# ORD_PT2399.net
KiCad netlist of a schematic drawn in Altium Designer
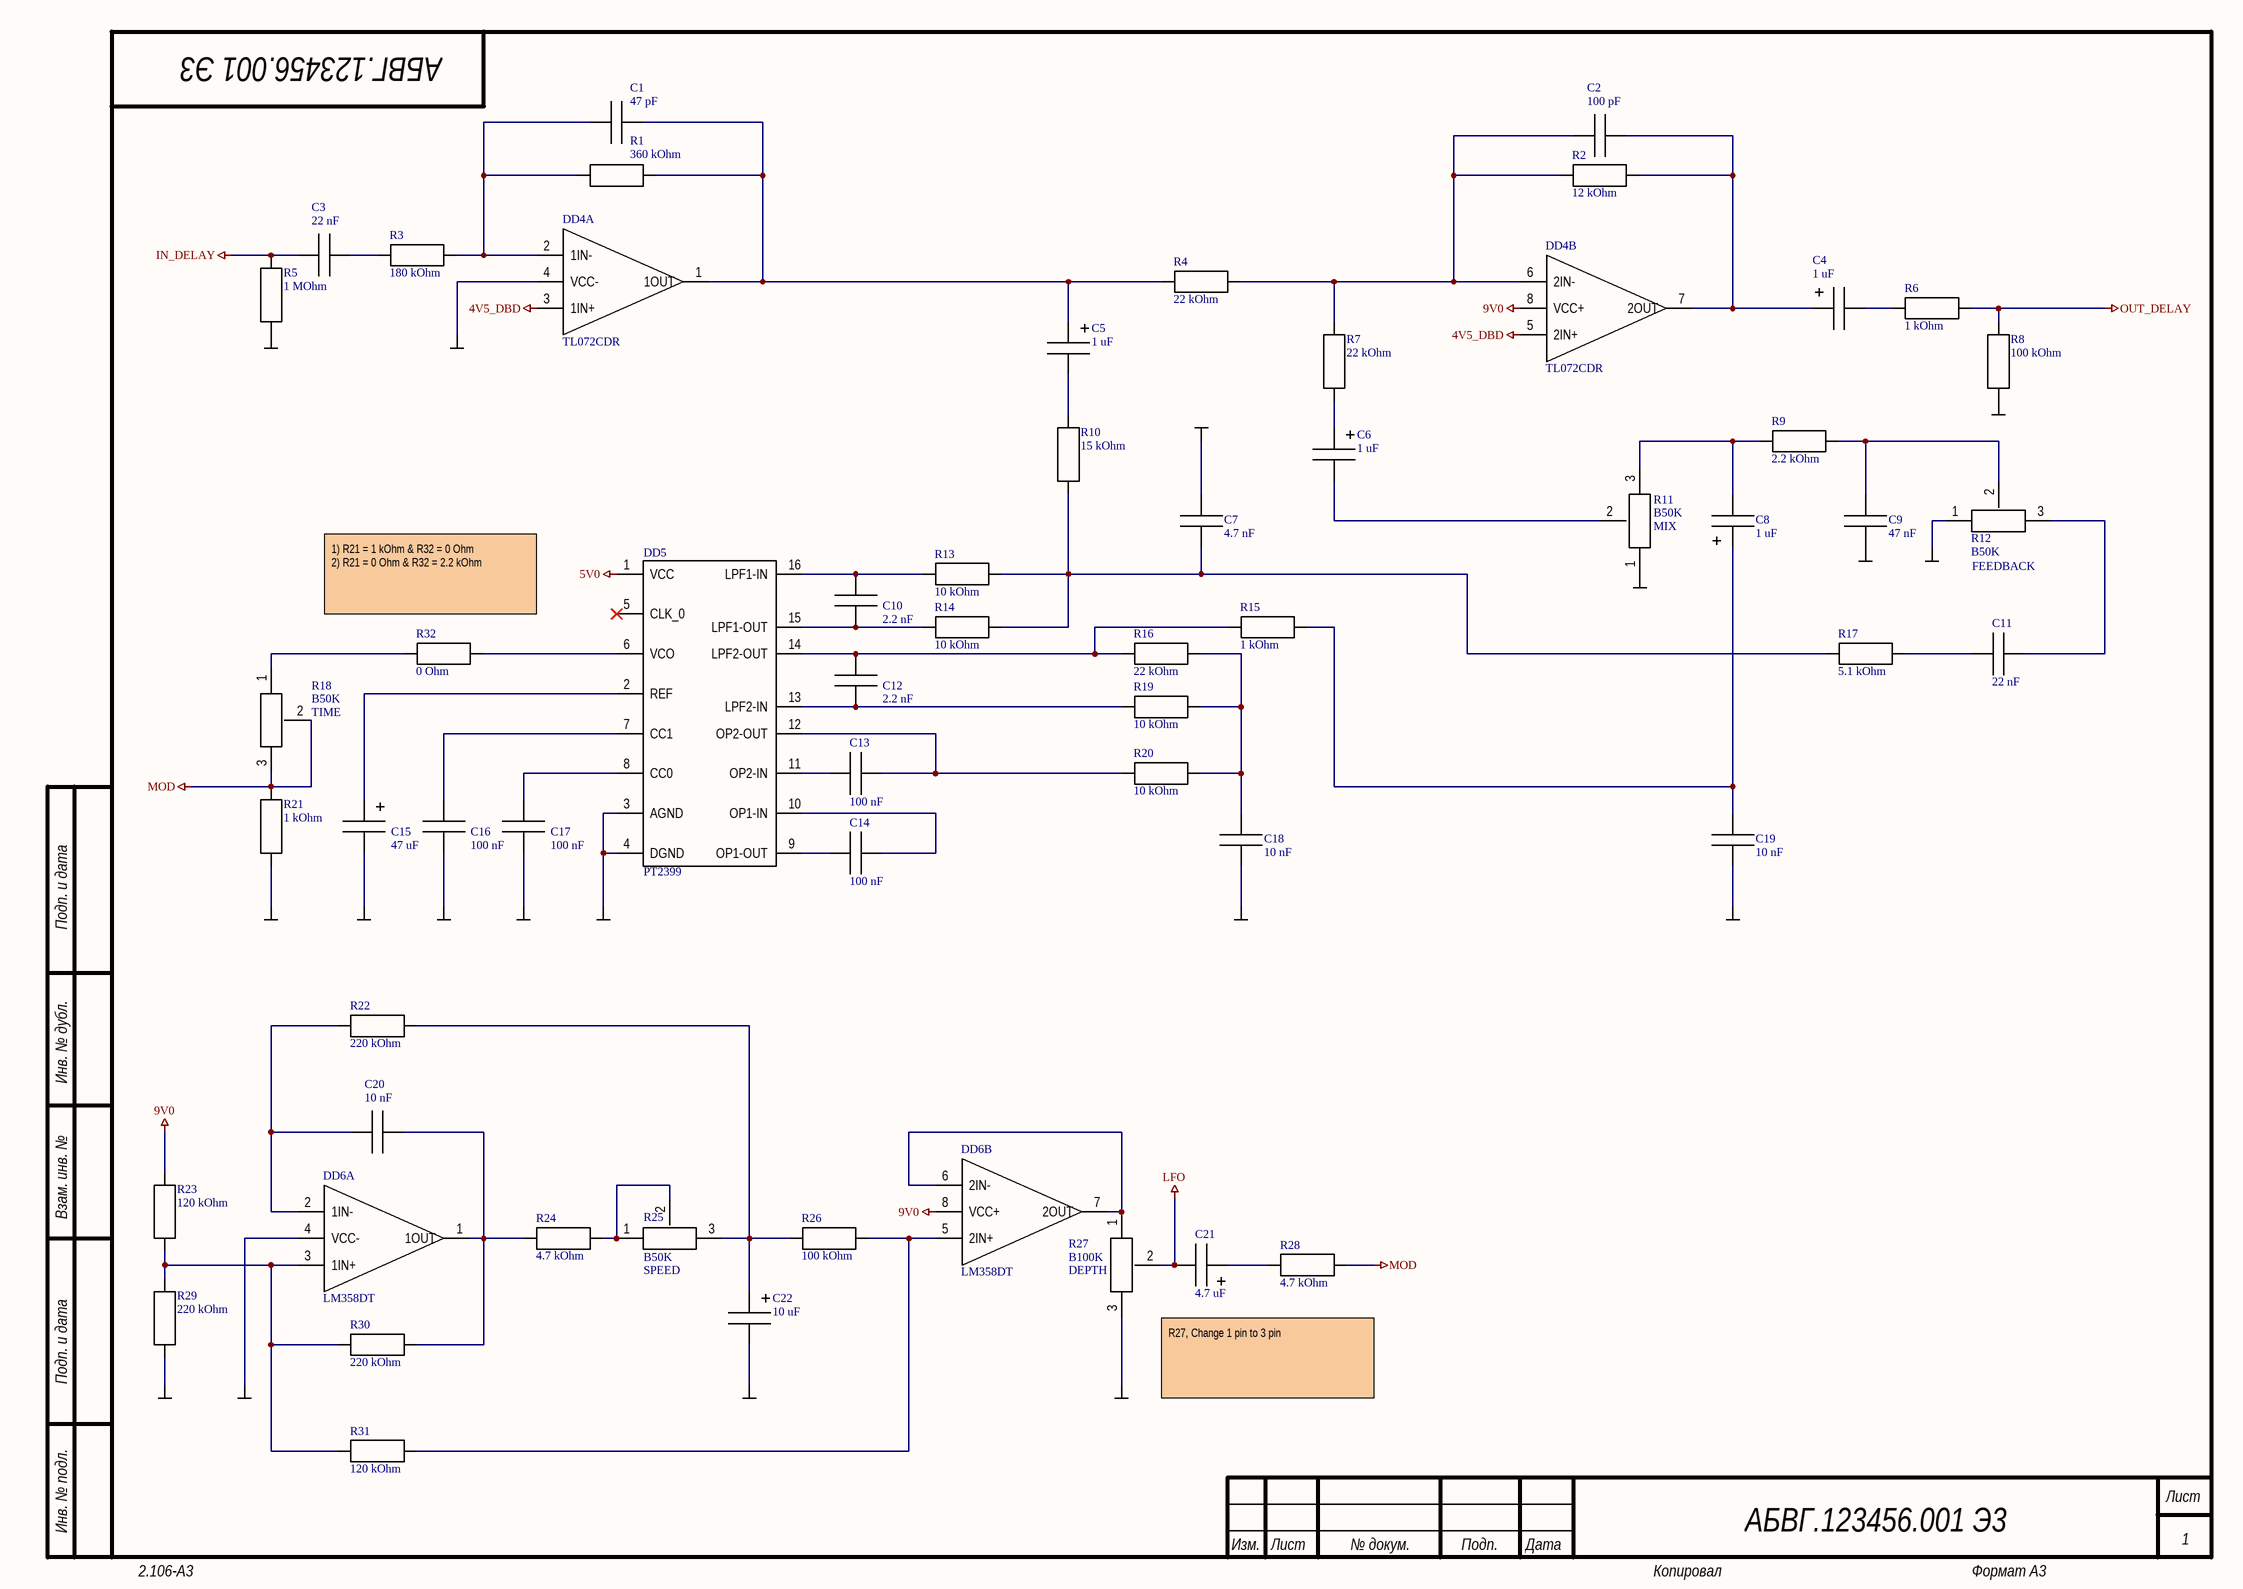
[diagram p0: ORD_PT2399.SchDoc]

(export (version "E")
  (design (tool "Eeschema 10.0.6"))
  (components
    (comp (ref "C1")
      (value "47 pF")
      (footprint "C0805[2012]")
      (libsource (lib "Gost_passive_lib") (part "Capacitor"))
    )
    (comp (ref "C2")
      (value "100 pF")
      (footprint "C0805[2012]")
      (libsource (lib "Gost_passive_lib") (part "Capacitor"))
    )
    (comp (ref "C3")
      (value "22 nF")
      (footprint "C0805[2012]")
      (libsource (lib "Gost_passive_lib") (part "Capacitor"))
    )
    (comp (ref "C4")
      (value "1 uF")
      (footprint "C3216_CASE-A")
      (libsource (lib "Gost_passive_lib") (part "Capacitor_Pol"))
    )
    (comp (ref "C5")
      (value "1 uF")
      (footprint "C3216_CASE-A")
      (libsource (lib "Gost_passive_lib") (part "Capacitor_Pol"))
    )
    (comp (ref "C6")
      (value "1 uF")
      (footprint "C3216_CASE-A")
      (libsource (lib "Gost_passive_lib") (part "Capacitor_Pol"))
    )
    (comp (ref "C7")
      (value "4.7 nF")
      (footprint "C0805[2012]")
      (libsource (lib "Gost_passive_lib") (part "Capacitor"))
    )
    (comp (ref "C8")
      (value "1 uF")
      (footprint "C3216_CASE-A")
      (libsource (lib "Gost_passive_lib") (part "Capacitor_Pol"))
    )
    (comp (ref "C9")
      (value "47 nF")
      (footprint "C0805[2012]")
      (libsource (lib "Gost_passive_lib") (part "Capacitor"))
    )
    (comp (ref "C10")
      (value "2.2 nF")
      (footprint "C0805[2012]")
      (libsource (lib "Gost_passive_lib") (part "Capacitor"))
    )
    (comp (ref "C11")
      (value "22 nF")
      (footprint "C0805[2012]")
      (libsource (lib "Gost_passive_lib") (part "Capacitor"))
    )
    (comp (ref "C12")
      (value "2.2 nF")
      (footprint "C0805[2012]")
      (libsource (lib "Gost_passive_lib") (part "Capacitor"))
    )
    (comp (ref "C13")
      (value "100 nF")
      (footprint "C0805[2012]")
      (libsource (lib "Gost_passive_lib") (part "Capacitor"))
    )
    (comp (ref "C14")
      (value "100 nF")
      (footprint "C0805[2012]")
      (libsource (lib "Gost_passive_lib") (part "Capacitor"))
    )
    (comp (ref "C15")
      (value "47 uF")
      (footprint "C3216_CASE-A")
      (libsource (lib "Gost_passive_lib") (part "Capacitor_Pol"))
    )
    (comp (ref "C16")
      (value "100 nF")
      (footprint "C0805[2012]")
      (libsource (lib "Gost_passive_lib") (part "Capacitor"))
    )
    (comp (ref "C17")
      (value "100 nF")
      (footprint "C0805[2012]")
      (libsource (lib "Gost_passive_lib") (part "Capacitor"))
    )
    (comp (ref "C18")
      (value "10 nF")
      (footprint "C0805[2012]")
      (libsource (lib "Gost_passive_lib") (part "Capacitor"))
    )
    (comp (ref "C19")
      (value "10 nF")
      (footprint "C0805[2012]")
      (libsource (lib "Gost_passive_lib") (part "Capacitor"))
    )
    (comp (ref "C20")
      (value "10 nF")
      (footprint "C0805[2012]")
      (libsource (lib "Gost_passive_lib") (part "Capacitor"))
    )
    (comp (ref "C21")
      (value "4.7 uF")
      (footprint "C3216_CASE-A")
      (libsource (lib "Gost_passive_lib") (part "Capacitor_Pol"))
    )
    (comp (ref "C22")
      (value "10 uF")
      (footprint "C3216_CASE-A")
      (libsource (lib "Gost_passive_lib") (part "Capacitor_Pol"))
    )
    (comp (ref "DD4")
      (value "TL072CDR")
      (footprint "SO8")
      (description "TL072CDR, Dual Operational Amplifier 4 MHz -18 to 18V, 8-Pin SO")
      (fields
        (field (name "MANUFACTURER_PART_NUMBER") "LM358DT")
        (field (name "MOUSER PART NUMBER") "511-LM358DT")
      )
      (libsource (lib "Gost_active_libs") (part "TL072CDR"))
    )
    (comp (ref "DD5")
      (value "PT2399")
      (footprint "DIP16_with_Socket")
      (description "Echo Processor IC")
      (libsource (lib "Gost_active_libs") (part "PT2399"))
    )
    (comp (ref "DD6")
      (value "LM358DT")
      (footprint "SO8")
      (description "LM358DT, Dual Operational Amplifier 1.1MHz 5 to 28V, 8-Pin SO")
      (fields (field (name "MOUSER PART NUMBER") "511-LM358DT") (field (name "RS PART NUMBER") "7140827P"))
      (libsource (lib "Gost_active_libs") (part "LM358DT"))
    )
    (comp (ref "R1")
      (value "360 kOhm")
      (footprint "R0805[2012]")
      (libsource (lib "Gost_passive_lib") (part "Resistor"))
    )
    (comp (ref "R2")
      (value "12 kOhm")
      (footprint "R0805[2012]")
      (libsource (lib "Gost_passive_lib") (part "Resistor"))
    )
    (comp (ref "R3")
      (value "180 kOhm")
      (footprint "R0805[2012]")
      (libsource (lib "Gost_passive_lib") (part "Resistor"))
    )
    (comp (ref "R4")
      (value "22 kOhm")
      (footprint "R0805[2012]")
      (libsource (lib "Gost_passive_lib") (part "Resistor"))
    )
    (comp (ref "R5")
      (value "1 MOhm")
      (footprint "R0805[2012]")
      (libsource (lib "Gost_passive_lib") (part "Resistor"))
    )
    (comp (ref "R6")
      (value "1 kOhm")
      (footprint "R0805[2012]")
      (libsource (lib "Gost_passive_lib") (part "Resistor"))
    )
    (comp (ref "R7")
      (value "22 kOhm")
      (footprint "R0805[2012]")
      (libsource (lib "Gost_passive_lib") (part "Resistor"))
    )
    (comp (ref "R8")
      (value "100 kOhm")
      (footprint "R0805[2012]")
      (libsource (lib "Gost_passive_lib") (part "Resistor"))
    )
    (comp (ref "R9")
      (value "2.2 kOhm")
      (footprint "R0805[2012]")
      (libsource (lib "Gost_passive_lib") (part "Resistor"))
    )
    (comp (ref "R10")
      (value "15 kOhm")
      (footprint "R0805[2012]")
      (libsource (lib "Gost_passive_lib") (part "Resistor"))
    )
    (comp (ref "R11")
      (value "B50K")
      (footprint "16K1")
      (libsource (lib "Gost_passive_lib") (part "16K1-B (Pot)"))
    )
    (comp (ref "R12")
      (value "B50K")
      (footprint "16K1")
      (libsource (lib "Gost_passive_lib") (part "16K1-B (Pot)"))
    )
    (comp (ref "R13")
      (value "10 kOhm")
      (footprint "R0805[2012]")
      (libsource (lib "Gost_passive_lib") (part "Resistor"))
    )
    (comp (ref "R14")
      (value "10 kOhm")
      (footprint "R0805[2012]")
      (libsource (lib "Gost_passive_lib") (part "Resistor"))
    )
    (comp (ref "R15")
      (value "1 kOhm")
      (footprint "R0805[2012]")
      (libsource (lib "Gost_passive_lib") (part "Resistor"))
    )
    (comp (ref "R16")
      (value "22 kOhm")
      (footprint "R0805[2012]")
      (libsource (lib "Gost_passive_lib") (part "Resistor"))
    )
    (comp (ref "R17")
      (value "5.1 kOhm")
      (footprint "R0805[2012]")
      (libsource (lib "Gost_passive_lib") (part "Resistor"))
    )
    (comp (ref "R18")
      (value "B50K")
      (footprint "16K1")
      (libsource (lib "Gost_passive_lib") (part "16K1-B (Pot)"))
    )
    (comp (ref "R19")
      (value "10 kOhm")
      (footprint "R0805[2012]")
      (libsource (lib "Gost_passive_lib") (part "Resistor"))
    )
    (comp (ref "R20")
      (value "10 kOhm")
      (footprint "R0805[2012]")
      (libsource (lib "Gost_passive_lib") (part "Resistor"))
    )
    (comp (ref "R21")
      (value "1 kOhm")
      (footprint "R0805[2012]")
      (libsource (lib "Gost_passive_lib") (part "Resistor"))
    )
    (comp (ref "R22")
      (value "220 kOhm")
      (footprint "R0805[2012]")
      (libsource (lib "Gost_passive_lib") (part "Resistor"))
    )
    (comp (ref "R23")
      (value "120 kOhm")
      (footprint "R0805[2012]")
      (libsource (lib "Gost_passive_lib") (part "Resistor"))
    )
    (comp (ref "R24")
      (value "4.7 kOhm")
      (footprint "R0805[2012]")
      (libsource (lib "Gost_passive_lib") (part "Resistor"))
    )
    (comp (ref "R25")
      (value "B50K")
      (footprint "16K1")
      (libsource (lib "Gost_passive_lib") (part "16K1-B (Pot)"))
    )
    (comp (ref "R26")
      (value "100 kOhm")
      (footprint "R0805[2012]")
      (libsource (lib "Gost_passive_lib") (part "Resistor"))
    )
    (comp (ref "R27")
      (value "B100K")
      (footprint "16K1")
      (libsource (lib "Gost_passive_lib") (part "16K1-B (Pot)"))
    )
    (comp (ref "R28")
      (value "4.7 kOhm")
      (footprint "R0805[2012]")
      (libsource (lib "Gost_passive_lib") (part "Resistor"))
    )
    (comp (ref "R29")
      (value "220 kOhm")
      (footprint "R0805[2012]")
      (libsource (lib "Gost_passive_lib") (part "Resistor"))
    )
    (comp (ref "R30")
      (value "220 kOhm")
      (footprint "R0805[2012]")
      (libsource (lib "Gost_passive_lib") (part "Resistor"))
    )
    (comp (ref "R31")
      (value "120 kOhm")
      (footprint "R0805[2012]")
      (libsource (lib "Gost_passive_lib") (part "Resistor"))
    )
    (comp (ref "R32")
      (value "0 Ohm")
      (footprint "R0805[2012]")
      (libsource (lib "Gost_passive_lib") (part "Resistor"))
    )
  )
  (nets
    (net (code "1") (name "4V5_DBD") (class "Default")
      (node (ref "DD4") (pin "3") (pinfunction "1IN+_3") (pintype "passive"))
      (node (ref "DD4") (pin "5") (pinfunction "2IN+_5") (pintype "passive"))
    )
    (net (code "2") (name "5V0") (class "Default")
      (node (ref "DD5") (pin "1") (pinfunction "VCC_1") (pintype "power_in"))
    )
    (net (code "3") (name "9V0") (class "Default")
      (node (ref "DD4") (pin "8") (pinfunction "VCC+_8") (pintype "power_in"))
      (node (ref "DD6") (pin "8") (pinfunction "VCC+_8") (pintype "power_in"))
      (node (ref "R23") (pin "1") (pinfunction "1_1") (pintype "passive"))
    )
    (net (code "4") (name "GND") (class "Default")
      (node (ref "C15") (pin "2") (pinfunction "2_2") (pintype "passive"))
      (node (ref "C16") (pin "1") (pinfunction "1_1") (pintype "passive"))
      (node (ref "C17") (pin "1") (pinfunction "1_1") (pintype "passive"))
      (node (ref "C18") (pin "2") (pinfunction "2_2") (pintype "passive"))
      (node (ref "C19") (pin "2") (pinfunction "2_2") (pintype "passive"))
      (node (ref "C22") (pin "2") (pinfunction "2_2") (pintype "passive"))
      (node (ref "C7") (pin "1") (pinfunction "1_1") (pintype "passive"))
      (node (ref "C9") (pin "2") (pinfunction "2_2") (pintype "passive"))
      (node (ref "DD4") (pin "4") (pinfunction "VCC-_4") (pintype "power_in"))
      (node (ref "DD5") (pin "3") (pinfunction "AGND_3") (pintype "passive"))
      (node (ref "DD5") (pin "4") (pinfunction "DGND_4") (pintype "passive"))
      (node (ref "DD6") (pin "4") (pinfunction "VCC-_4") (pintype "power_in"))
      (node (ref "R11") (pin "1") (pinfunction "1_1") (pintype "passive"))
      (node (ref "R12") (pin "1") (pinfunction "1_1") (pintype "passive"))
      (node (ref "R21") (pin "1") (pinfunction "1_1") (pintype "passive"))
      (node (ref "R27") (pin "3") (pinfunction "3_3") (pintype "passive"))
      (node (ref "R29") (pin "2") (pinfunction "2_2") (pintype "passive"))
      (node (ref "R5") (pin "1") (pinfunction "1_1") (pintype "passive"))
      (node (ref "R8") (pin "2") (pinfunction "2_2") (pintype "passive"))
    )
    (net (code "5") (name "IN_DELAY") (class "Default")
      (node (ref "C3") (pin "1") (pinfunction "1_1") (pintype "passive"))
      (node (ref "R5") (pin "2") (pinfunction "2_2") (pintype "passive"))
    )
    (net (code "6") (name "LFO") (class "Default")
      (node (ref "C21") (pin "2") (pinfunction "2_2") (pintype "passive"))
      (node (ref "R27") (pin "2") (pinfunction "2_2") (pintype "passive"))
    )
    (net (code "7") (name "MOD") (class "Default")
      (node (ref "R18") (pin "2") (pinfunction "2_2") (pintype "passive"))
      (node (ref "R18") (pin "3") (pinfunction "3_3") (pintype "passive"))
      (node (ref "R21") (pin "2") (pinfunction "2_2") (pintype "passive"))
      (node (ref "R28") (pin "2") (pinfunction "2_2") (pintype "passive"))
    )
    (net (code "8") (name "Net-(C3-Pad2)") (class "Default")
      (node (ref "C3") (pin "2") (pinfunction "2_2") (pintype "passive"))
      (node (ref "R3") (pin "2") (pinfunction "2_2") (pintype "passive"))
    )
    (net (code "9") (name "Net-(C4-Pad2)") (class "Default")
      (node (ref "C4") (pin "2") (pinfunction "2_2") (pintype "passive"))
      (node (ref "R6") (pin "2") (pinfunction "2_2") (pintype "passive"))
    )
    (net (code "10") (name "Net-(C5-Pad2)") (class "Default")
      (node (ref "C5") (pin "2") (pinfunction "2_2") (pintype "passive"))
      (node (ref "R10") (pin "1") (pinfunction "1_1") (pintype "passive"))
    )
    (net (code "11") (name "Net-(C6-Pad1)") (class "Default")
      (node (ref "C6") (pin "1") (pinfunction "1_1") (pintype "passive"))
      (node (ref "R7") (pin "2") (pinfunction "2_2") (pintype "passive"))
    )
    (net (code "12") (name "Net-(C6-Pad2)") (class "Default")
      (node (ref "C6") (pin "2") (pinfunction "2_2") (pintype "passive"))
      (node (ref "R11") (pin "2") (pinfunction "2_2") (pintype "passive"))
    )
    (net (code "13") (name "Net-(C7-Pad2)") (class "Default")
      (node (ref "C7") (pin "2") (pinfunction "2_2") (pintype "passive"))
      (node (ref "R10") (pin "2") (pinfunction "2_2") (pintype "passive"))
      (node (ref "R13") (pin "2") (pinfunction "2_2") (pintype "passive"))
      (node (ref "R14") (pin "2") (pinfunction "2_2") (pintype "passive"))
      (node (ref "R17") (pin "1") (pinfunction "1_1") (pintype "passive"))
    )
    (net (code "14") (name "Net-(C8-Pad2)") (class "Default")
      (node (ref "C8") (pin "2") (pinfunction "2_2") (pintype "passive"))
      (node (ref "R11") (pin "3") (pinfunction "3_3") (pintype "passive"))
      (node (ref "R9") (pin "1") (pinfunction "1_1") (pintype "passive"))
    )
    (net (code "15") (name "Net-(C9-Pad1)") (class "Default")
      (node (ref "C9") (pin "1") (pinfunction "1_1") (pintype "passive"))
      (node (ref "R12") (pin "2") (pinfunction "2_2") (pintype "passive"))
      (node (ref "R9") (pin "2") (pinfunction "2_2") (pintype "passive"))
    )
    (net (code "16") (name "Net-(C11-Pad1)") (class "Default")
      (node (ref "C11") (pin "1") (pinfunction "1_1") (pintype "passive"))
      (node (ref "R17") (pin "2") (pinfunction "2_2") (pintype "passive"))
    )
    (net (code "17") (name "Net-(C11-Pad2)") (class "Default")
      (node (ref "C11") (pin "2") (pinfunction "2_2") (pintype "passive"))
      (node (ref "R12") (pin "3") (pinfunction "3_3") (pintype "passive"))
    )
    (net (code "18") (name "Net-(C18-Pad1)") (class "Default")
      (node (ref "C18") (pin "1") (pinfunction "1_1") (pintype "passive"))
      (node (ref "R16") (pin "2") (pinfunction "2_2") (pintype "passive"))
      (node (ref "R19") (pin "2") (pinfunction "2_2") (pintype "passive"))
      (node (ref "R20") (pin "2") (pinfunction "2_2") (pintype "passive"))
    )
    (net (code "19") (name "Net-(C19-Pad1)") (class "Default")
      (node (ref "C19") (pin "1") (pinfunction "1_1") (pintype "passive"))
      (node (ref "C8") (pin "1") (pinfunction "1_1") (pintype "passive"))
      (node (ref "R15") (pin "2") (pinfunction "2_2") (pintype "passive"))
    )
    (net (code "20") (name "Net-(C21-Pad1)") (class "Default")
      (node (ref "C21") (pin "1") (pinfunction "1_1") (pintype "passive"))
      (node (ref "R28") (pin "1") (pinfunction "1_1") (pintype "passive"))
    )
    (net (code "21") (name "Net-(C22-Pad1)") (class "Default")
      (node (ref "C22") (pin "1") (pinfunction "1_1") (pintype "passive"))
      (node (ref "R22") (pin "2") (pinfunction "2_2") (pintype "passive"))
      (node (ref "R25") (pin "3") (pinfunction "3_3") (pintype "passive"))
      (node (ref "R26") (pin "1") (pinfunction "1_1") (pintype "passive"))
    )
    (net (code "22") (name "Net-(DD4A-1IN-)") (class "Default")
      (node (ref "C1") (pin "1") (pinfunction "1_1") (pintype "passive"))
      (node (ref "DD4") (pin "2") (pinfunction "1IN-_2") (pintype "passive"))
      (node (ref "R1") (pin "2") (pinfunction "2_2") (pintype "passive"))
      (node (ref "R3") (pin "1") (pinfunction "1_1") (pintype "passive"))
    )
    (net (code "23") (name "Net-(DD4A-1OUT)") (class "Default")
      (node (ref "C1") (pin "2") (pinfunction "2_2") (pintype "passive"))
      (node (ref "C5") (pin "1") (pinfunction "1_1") (pintype "passive"))
      (node (ref "DD4") (pin "1") (pinfunction "1OUT_1") (pintype "passive"))
      (node (ref "R1") (pin "1") (pinfunction "1_1") (pintype "passive"))
      (node (ref "R4") (pin "2") (pinfunction "2_2") (pintype "passive"))
    )
    (net (code "24") (name "Net-(DD4B-2IN-)") (class "Default")
      (node (ref "C2") (pin "1") (pinfunction "1_1") (pintype "passive"))
      (node (ref "DD4") (pin "6") (pinfunction "2IN-_6") (pintype "passive"))
      (node (ref "R2") (pin "2") (pinfunction "2_2") (pintype "passive"))
      (node (ref "R4") (pin "1") (pinfunction "1_1") (pintype "passive"))
      (node (ref "R7") (pin "1") (pinfunction "1_1") (pintype "passive"))
    )
    (net (code "25") (name "Net-(DD4B-2OUT)") (class "Default")
      (node (ref "C2") (pin "2") (pinfunction "2_2") (pintype "passive"))
      (node (ref "C4") (pin "1") (pinfunction "1_1") (pintype "passive"))
      (node (ref "DD4") (pin "7") (pinfunction "2OUT_7") (pintype "passive"))
      (node (ref "R2") (pin "1") (pinfunction "1_1") (pintype "passive"))
    )
    (net (code "26") (name "Net-(DD5-CC0)") (class "Default")
      (node (ref "C17") (pin "2") (pinfunction "2_2") (pintype "passive"))
      (node (ref "DD5") (pin "8") (pinfunction "CC0_8") (pintype "passive"))
    )
    (net (code "27") (name "Net-(DD5-CC1)") (class "Default")
      (node (ref "C16") (pin "2") (pinfunction "2_2") (pintype "passive"))
      (node (ref "DD5") (pin "7") (pinfunction "CC1_7") (pintype "passive"))
    )
    (net (code "28") (name "Net-(DD5-LPF1-IN)") (class "Default")
      (node (ref "C10") (pin "2") (pinfunction "2_2") (pintype "passive"))
      (node (ref "DD5") (pin "16") (pinfunction "LPF1-IN_16") (pintype "passive"))
      (node (ref "R13") (pin "1") (pinfunction "1_1") (pintype "passive"))
    )
    (net (code "29") (name "Net-(DD5-LPF1-OUT)") (class "Default")
      (node (ref "C10") (pin "1") (pinfunction "1_1") (pintype "passive"))
      (node (ref "DD5") (pin "15") (pinfunction "LPF1-OUT_15") (pintype "passive"))
      (node (ref "R14") (pin "1") (pinfunction "1_1") (pintype "passive"))
    )
    (net (code "30") (name "Net-(DD5-LPF2-IN)") (class "Default")
      (node (ref "C12") (pin "1") (pinfunction "1_1") (pintype "passive"))
      (node (ref "DD5") (pin "13") (pinfunction "LPF2-IN_13") (pintype "passive"))
      (node (ref "R19") (pin "1") (pinfunction "1_1") (pintype "passive"))
    )
    (net (code "31") (name "Net-(DD5-LPF2-OUT)") (class "Default")
      (node (ref "C12") (pin "2") (pinfunction "2_2") (pintype "passive"))
      (node (ref "DD5") (pin "14") (pinfunction "LPF2-OUT_14") (pintype "passive"))
      (node (ref "R15") (pin "1") (pinfunction "1_1") (pintype "passive"))
      (node (ref "R16") (pin "1") (pinfunction "1_1") (pintype "passive"))
    )
    (net (code "32") (name "Net-(DD5-OP1-IN)") (class "Default")
      (node (ref "C14") (pin "1") (pinfunction "1_1") (pintype "passive"))
      (node (ref "DD5") (pin "10") (pinfunction "OP1-IN_10") (pintype "passive"))
    )
    (net (code "33") (name "Net-(DD5-OP1-OUT)") (class "Default")
      (node (ref "C14") (pin "2") (pinfunction "2_2") (pintype "passive"))
      (node (ref "DD5") (pin "9") (pinfunction "OP1-OUT_9") (pintype "passive"))
    )
    (net (code "34") (name "Net-(DD5-OP2-IN)") (class "Default")
      (node (ref "C13") (pin "2") (pinfunction "2_2") (pintype "passive"))
      (node (ref "DD5") (pin "11") (pinfunction "OP2-IN_11") (pintype "passive"))
    )
    (net (code "35") (name "Net-(DD5-OP2-OUT)") (class "Default")
      (node (ref "C13") (pin "1") (pinfunction "1_1") (pintype "passive"))
      (node (ref "DD5") (pin "12") (pinfunction "OP2-OUT_12") (pintype "passive"))
      (node (ref "R20") (pin "1") (pinfunction "1_1") (pintype "passive"))
    )
    (net (code "36") (name "Net-(DD5-REF)") (class "Default")
      (node (ref "C15") (pin "1") (pinfunction "1_1") (pintype "passive"))
      (node (ref "DD5") (pin "2") (pinfunction "REF_2") (pintype "passive"))
    )
    (net (code "37") (name "Net-(DD5-VCO)") (class "Default")
      (node (ref "DD5") (pin "6") (pinfunction "VCO_6") (pintype "passive"))
      (node (ref "R32") (pin "1") (pinfunction "1_1") (pintype "passive"))
    )
    (net (code "38") (name "Net-(DD6A-1IN+)") (class "Default")
      (node (ref "DD6") (pin "3") (pinfunction "1IN+_3") (pintype "passive"))
      (node (ref "R23") (pin "2") (pinfunction "2_2") (pintype "passive"))
      (node (ref "R29") (pin "1") (pinfunction "1_1") (pintype "passive"))
      (node (ref "R30") (pin "1") (pinfunction "1_1") (pintype "passive"))
      (node (ref "R31") (pin "1") (pinfunction "1_1") (pintype "passive"))
    )
    (net (code "39") (name "Net-(DD6A-1IN-)") (class "Default")
      (node (ref "C20") (pin "1") (pinfunction "1_1") (pintype "passive"))
      (node (ref "DD6") (pin "2") (pinfunction "1IN-_2") (pintype "passive"))
      (node (ref "R22") (pin "1") (pinfunction "1_1") (pintype "passive"))
    )
    (net (code "40") (name "Net-(DD6A-1OUT)") (class "Default")
      (node (ref "C20") (pin "2") (pinfunction "2_2") (pintype "passive"))
      (node (ref "DD6") (pin "1") (pinfunction "1OUT_1") (pintype "passive"))
      (node (ref "R24") (pin "1") (pinfunction "1_1") (pintype "passive"))
      (node (ref "R30") (pin "2") (pinfunction "2_2") (pintype "passive"))
    )
    (net (code "41") (name "Net-(DD6B-2IN+)") (class "Default")
      (node (ref "DD6") (pin "5") (pinfunction "2IN+_5") (pintype "passive"))
      (node (ref "R26") (pin "2") (pinfunction "2_2") (pintype "passive"))
      (node (ref "R31") (pin "2") (pinfunction "2_2") (pintype "passive"))
    )
    (net (code "42") (name "Net-(DD6B-2IN-)") (class "Default")
      (node (ref "DD6") (pin "6") (pinfunction "2IN-_6") (pintype "passive"))
      (node (ref "DD6") (pin "7") (pinfunction "2OUT_7") (pintype "passive"))
      (node (ref "R27") (pin "1") (pinfunction "1_1") (pintype "passive"))
    )
    (net (code "43") (name "Net-(R18-Pad1)") (class "Default")
      (node (ref "R18") (pin "1") (pinfunction "1_1") (pintype "passive"))
      (node (ref "R32") (pin "2") (pinfunction "2_2") (pintype "passive"))
    )
    (net (code "44") (name "Net-(R24-Pad2)") (class "Default")
      (node (ref "R24") (pin "2") (pinfunction "2_2") (pintype "passive"))
      (node (ref "R25") (pin "1") (pinfunction "1_1") (pintype "passive"))
      (node (ref "R25") (pin "2") (pinfunction "2_2") (pintype "passive"))
    )
    (net (code "45") (name "OUT_DELAY") (class "Default")
      (node (ref "R6") (pin "1") (pinfunction "1_1") (pintype "passive"))
      (node (ref "R8") (pin "1") (pinfunction "1_1") (pintype "passive"))
    )
    (net (code "46") (name "unconnected-(DD5-CLK_0-Pad5)") (class "Default")
      (node (ref "DD5") (pin "5") (pinfunction "CLK_0_5") (pintype "passive+no_connect"))
    )
  )
)
